# Eitech-Robotics_v11.net
KiCad netlist of a schematic drawn in EAGLE
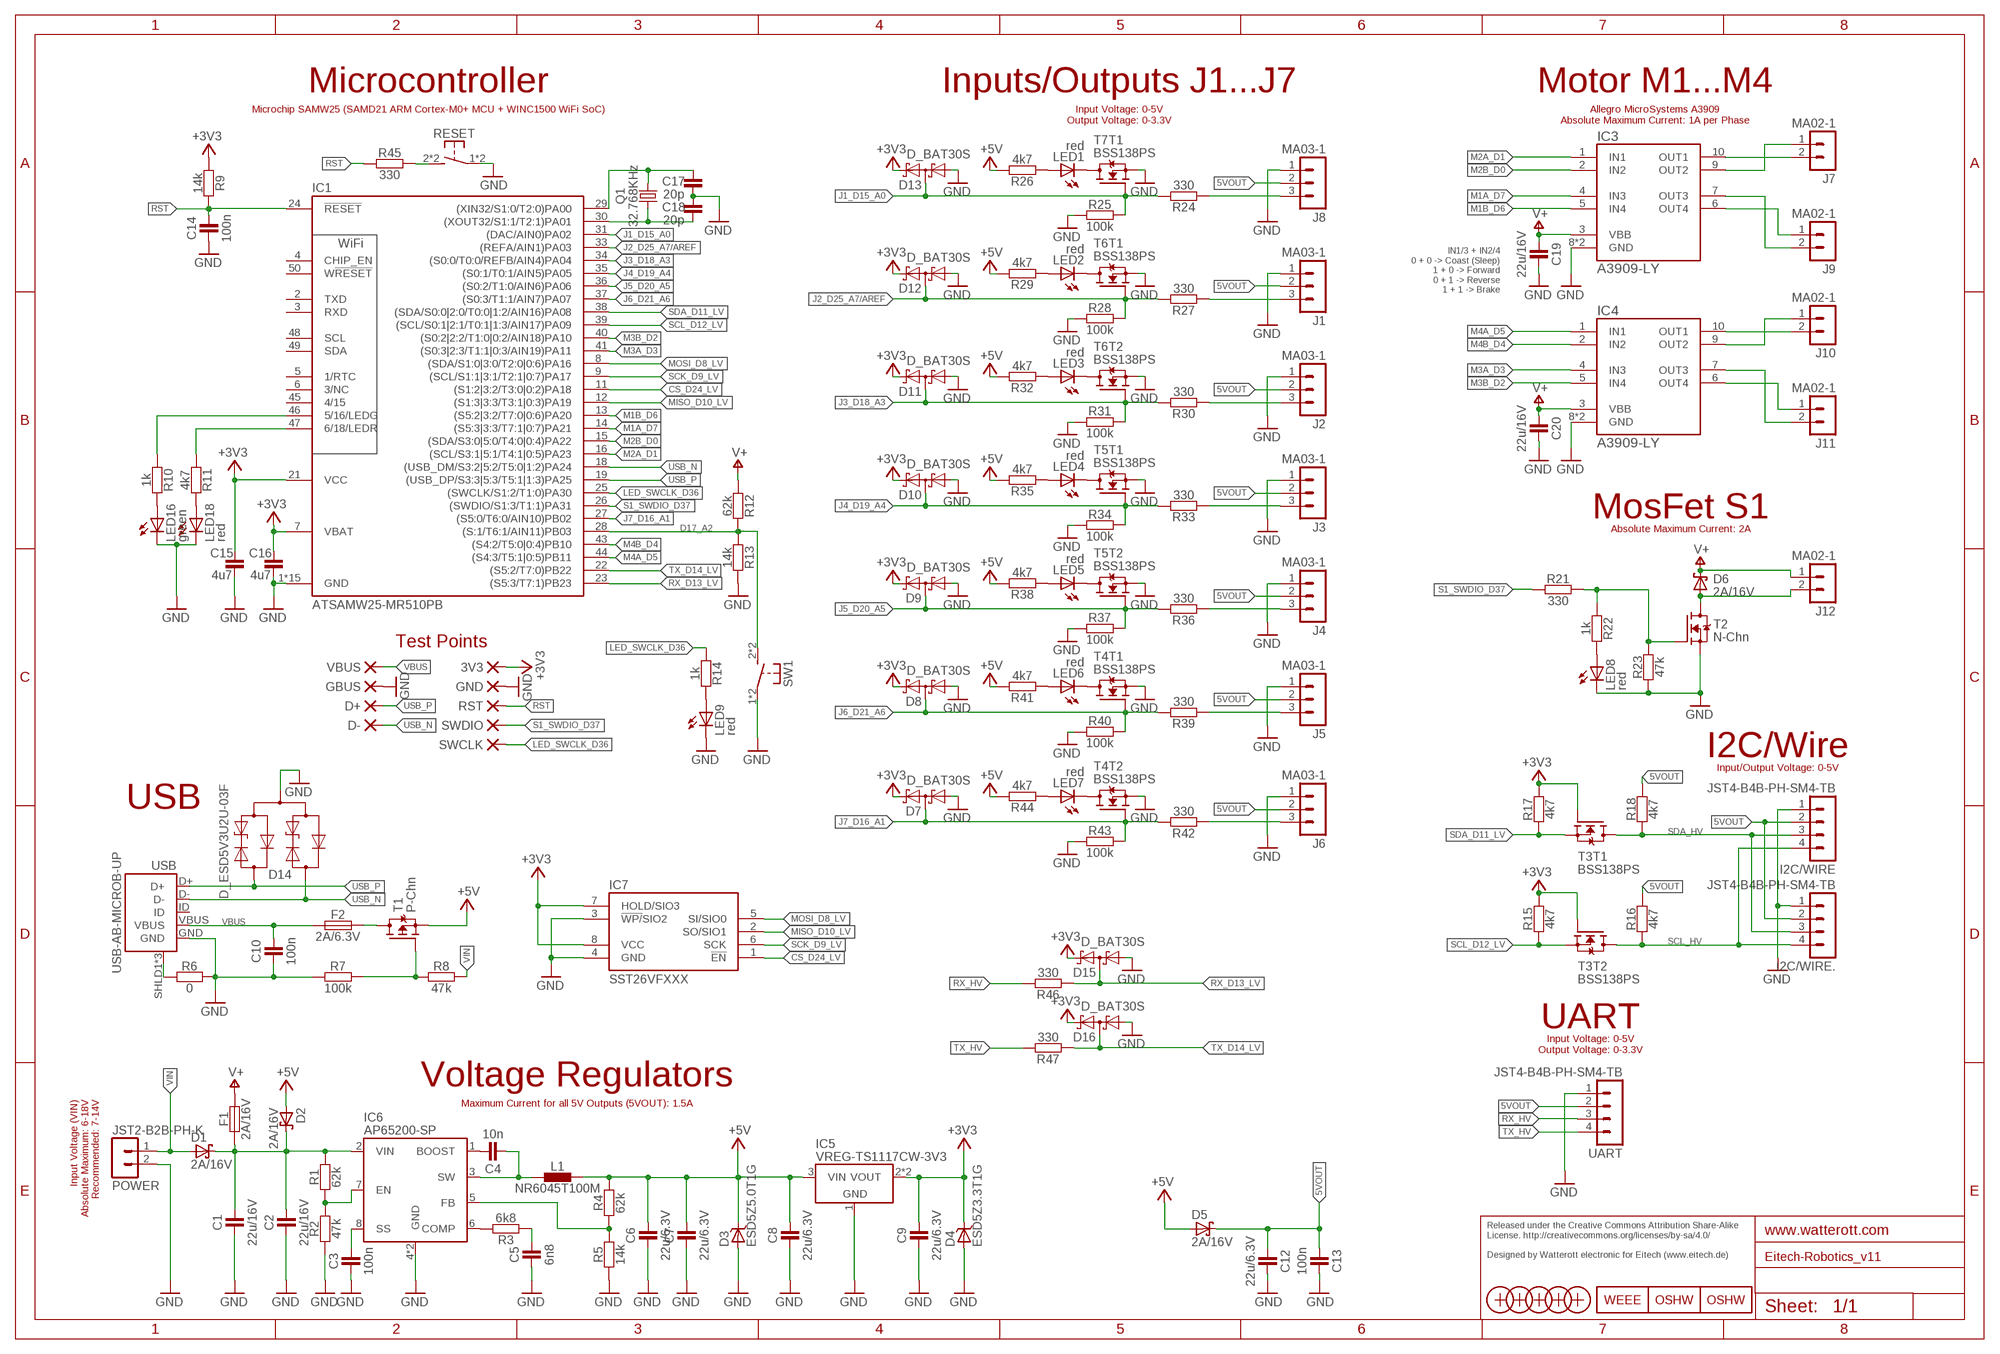
[diagram p0: schematic, sheet 1]

(export (version "E")
  (design (tool "Eeschema 10.0.6"))
  (components
    (comp (ref "3V3")
      (value "PAD-1.0_NC")
      (footprint "eagle-import:PAD-1.0_NC")
      (libsource (lib "eagle-import") (part "PAD-1.0_NC"))
    )
    (comp (ref "C1")
      (value "22u/16V")
      (footprint "eagle-import:C0805")
      (libsource (lib "eagle-import") (part "CAPACITOR-0805"))
    )
    (comp (ref "C2")
      (value "22u/16V")
      (footprint "eagle-import:C0805")
      (libsource (lib "eagle-import") (part "CAPACITOR-0805"))
    )
    (comp (ref "C3")
      (value "100n")
      (footprint "eagle-import:C0402")
      (libsource (lib "eagle-import") (part "CAPACITOR-0402"))
    )
    (comp (ref "C4")
      (value "10n")
      (footprint "eagle-import:C0402")
      (libsource (lib "eagle-import") (part "CAPACITOR-0402"))
    )
    (comp (ref "C5")
      (value "6n8")
      (footprint "eagle-import:C0402")
      (libsource (lib "eagle-import") (part "CAPACITOR-0402"))
    )
    (comp (ref "C6")
      (value "22u/6.3V")
      (footprint "eagle-import:C0805")
      (libsource (lib "eagle-import") (part "CAPACITOR-0805"))
    )
    (comp (ref "C7")
      (value "22u/6.3V")
      (footprint "eagle-import:C0805")
      (libsource (lib "eagle-import") (part "CAPACITOR-0805"))
    )
    (comp (ref "C8")
      (value "22u/6.3V")
      (footprint "eagle-import:C0805")
      (libsource (lib "eagle-import") (part "CAPACITOR-0805"))
    )
    (comp (ref "C9")
      (value "22u/6.3V")
      (footprint "eagle-import:C0805")
      (libsource (lib "eagle-import") (part "CAPACITOR-0805"))
    )
    (comp (ref "C10")
      (value "100n")
      (footprint "eagle-import:C0402")
      (libsource (lib "eagle-import") (part "CAPACITOR-0402"))
    )
    (comp (ref "C12")
      (value "22u/6.3V")
      (footprint "eagle-import:C0805")
      (libsource (lib "eagle-import") (part "CAPACITOR-0805"))
    )
    (comp (ref "C13")
      (value "100n")
      (footprint "eagle-import:C0402")
      (libsource (lib "eagle-import") (part "CAPACITOR-0402"))
    )
    (comp (ref "C14")
      (value "100n")
      (footprint "eagle-import:C0402")
      (libsource (lib "eagle-import") (part "CAPACITOR-0402"))
    )
    (comp (ref "C15")
      (value "4u7")
      (footprint "eagle-import:C0603")
      (libsource (lib "eagle-import") (part "CAPACITOR-0603"))
    )
    (comp (ref "C16")
      (value "4u7")
      (footprint "eagle-import:C0603")
      (libsource (lib "eagle-import") (part "CAPACITOR-0603"))
    )
    (comp (ref "C17")
      (value "20p")
      (footprint "eagle-import:C0402")
      (libsource (lib "eagle-import") (part "CAPACITOR-0402"))
    )
    (comp (ref "C18")
      (value "20p")
      (footprint "eagle-import:C0402")
      (libsource (lib "eagle-import") (part "CAPACITOR-0402"))
    )
    (comp (ref "C19")
      (value "22u/16V")
      (footprint "eagle-import:C0805")
      (libsource (lib "eagle-import") (part "CAPACITOR-0805"))
    )
    (comp (ref "C20")
      (value "22u/16V")
      (footprint "eagle-import:C0805")
      (libsource (lib "eagle-import") (part "CAPACITOR-0805"))
    )
    (comp (ref "D+")
      (value "PAD-1.0_NC")
      (footprint "eagle-import:PAD-1.0_NC")
      (libsource (lib "eagle-import") (part "PAD-1.0_NC"))
    )
    (comp (ref "D-")
      (value "PAD-1.0_NC")
      (footprint "eagle-import:PAD-1.0_NC")
      (libsource (lib "eagle-import") (part "PAD-1.0_NC"))
    )
    (comp (ref "D1")
      (value "2A/16V")
      (footprint "eagle-import:SOD123")
      (libsource (lib "eagle-import") (part "D_SCHOTTKY-SOD123"))
    )
    (comp (ref "D2")
      (value "2A/16V")
      (footprint "eagle-import:SOD123")
      (libsource (lib "eagle-import") (part "D_SCHOTTKY-SOD123"))
    )
    (comp (ref "D3")
      (value "ESD5Z5.0T1G")
      (footprint "eagle-import:SOD523")
      (libsource (lib "eagle-import") (part "D_TVS-SOD523"))
    )
    (comp (ref "D4")
      (value "ESD5Z3.3T1G")
      (footprint "eagle-import:SOD523")
      (libsource (lib "eagle-import") (part "D_TVS-SOD523"))
    )
    (comp (ref "D5")
      (value "2A/16V")
      (footprint "eagle-import:SOD123")
      (libsource (lib "eagle-import") (part "D_SCHOTTKY-SOD123"))
    )
    (comp (ref "D6")
      (value "2A/16V")
      (footprint "eagle-import:SOD123")
      (libsource (lib "eagle-import") (part "D_SCHOTTKY-SOD123"))
    )
    (comp (ref "D7")
      (value "D_BAT30S")
      (footprint "eagle-import:SOT323")
      (libsource (lib "eagle-import") (part "D_BAT30S"))
    )
    (comp (ref "D8")
      (value "D_BAT30S")
      (footprint "eagle-import:SOT323")
      (libsource (lib "eagle-import") (part "D_BAT30S"))
    )
    (comp (ref "D9")
      (value "D_BAT30S")
      (footprint "eagle-import:SOT323")
      (libsource (lib "eagle-import") (part "D_BAT30S"))
    )
    (comp (ref "D10")
      (value "D_BAT30S")
      (footprint "eagle-import:SOT323")
      (libsource (lib "eagle-import") (part "D_BAT30S"))
    )
    (comp (ref "D11")
      (value "D_BAT30S")
      (footprint "eagle-import:SOT323")
      (libsource (lib "eagle-import") (part "D_BAT30S"))
    )
    (comp (ref "D12")
      (value "D_BAT30S")
      (footprint "eagle-import:SOT323")
      (libsource (lib "eagle-import") (part "D_BAT30S"))
    )
    (comp (ref "D13")
      (value "D_BAT30S")
      (footprint "eagle-import:SOT323")
      (libsource (lib "eagle-import") (part "D_BAT30S"))
    )
    (comp (ref "D14")
      (value "D_ESD5V3U2U-03F")
      (footprint "eagle-import:SOT723")
      (libsource (lib "eagle-import") (part "D_ESD5V3U2U-03F"))
    )
    (comp (ref "D15")
      (value "D_BAT30S")
      (footprint "eagle-import:SOT323")
      (libsource (lib "eagle-import") (part "D_BAT30S"))
    )
    (comp (ref "D16")
      (value "D_BAT30S")
      (footprint "eagle-import:SOT323")
      (libsource (lib "eagle-import") (part "D_BAT30S"))
    )
    (comp (ref "F1")
      (value "2A/16V")
      (footprint "eagle-import:C1812")
      (libsource (lib "eagle-import") (part "FUSE-1812"))
    )
    (comp (ref "F2")
      (value "2A/6.3V")
      (footprint "eagle-import:C1206")
      (libsource (lib "eagle-import") (part "FUSE-1206"))
    )
    (comp (ref "GBUS")
      (value "PAD-1.0_NC")
      (footprint "eagle-import:PAD-1.0_NC")
      (libsource (lib "eagle-import") (part "PAD-1.0_NC"))
    )
    (comp (ref "GND")
      (value "PAD-1.0_NC")
      (footprint "eagle-import:PAD-1.0_NC")
      (libsource (lib "eagle-import") (part "PAD-1.0_NC"))
    )
    (comp (ref "I2C/WIRE")
      (value "JST4-B4B-PH-SM4-TB")
      (footprint "eagle-import:JST_B4B-PH-SM4-TB")
      (libsource (lib "eagle-import") (part "JST4-B4B-PH-SM4-TB"))
    )
    (comp (ref "I2C/WIRE.")
      (value "JST4-B4B-PH-SM4-TB")
      (footprint "eagle-import:JST_B4B-PH-SM4-TB")
      (libsource (lib "eagle-import") (part "JST4-B4B-PH-SM4-TB"))
    )
    (comp (ref "IC1")
      (value "ATSAMW25-MR510PB")
      (footprint "eagle-import:ATSAMW25-MRX10")
      (libsource (lib "eagle-import") (part "ATSAMW25-MR510PB"))
    )
    (comp (ref "IC3")
      (value "A3909-LY")
      (footprint "eagle-import:MSOP10-PAD")
      (libsource (lib "eagle-import") (part "A3909-LY"))
    )
    (comp (ref "IC4")
      (value "A3909-LY")
      (footprint "eagle-import:MSOP10-PAD")
      (libsource (lib "eagle-import") (part "A3909-LY"))
    )
    (comp (ref "IC5")
      (value "VREG-TS1117CW-3V3")
      (footprint "eagle-import:SOT223")
      (libsource (lib "eagle-import") (part "VREG-TS1117CW-3V3"))
    )
    (comp (ref "IC6")
      (value "AP65200-SP")
      (footprint "eagle-import:SO08-PAD")
      (libsource (lib "eagle-import") (part "AP65200-SP"))
    )
    (comp (ref "IC7")
      (value "SST26VFXXX")
      (footprint "eagle-import:SO08")
      (libsource (lib "eagle-import") (part "SST26VFXXX"))
    )
    (comp (ref "J1")
      (value "MA03-1")
      (footprint "eagle-import:MA03-1")
      (libsource (lib "eagle-import") (part "MA03-1"))
    )
    (comp (ref "J2")
      (value "MA03-1")
      (footprint "eagle-import:MA03-1")
      (libsource (lib "eagle-import") (part "MA03-1"))
    )
    (comp (ref "J3")
      (value "MA03-1")
      (footprint "eagle-import:MA03-1")
      (libsource (lib "eagle-import") (part "MA03-1"))
    )
    (comp (ref "J4")
      (value "MA03-1")
      (footprint "eagle-import:MA03-1")
      (libsource (lib "eagle-import") (part "MA03-1"))
    )
    (comp (ref "J5")
      (value "MA03-1")
      (footprint "eagle-import:MA03-1")
      (libsource (lib "eagle-import") (part "MA03-1"))
    )
    (comp (ref "J6")
      (value "MA03-1")
      (footprint "eagle-import:MA03-1")
      (libsource (lib "eagle-import") (part "MA03-1"))
    )
    (comp (ref "J7")
      (value "MA02-1")
      (footprint "eagle-import:MA02-1")
      (libsource (lib "eagle-import") (part "MA02-1"))
    )
    (comp (ref "J8")
      (value "MA03-1")
      (footprint "eagle-import:MA03-1")
      (libsource (lib "eagle-import") (part "MA03-1"))
    )
    (comp (ref "J9")
      (value "MA02-1")
      (footprint "eagle-import:MA02-1")
      (libsource (lib "eagle-import") (part "MA02-1"))
    )
    (comp (ref "J10")
      (value "MA02-1")
      (footprint "eagle-import:MA02-1")
      (libsource (lib "eagle-import") (part "MA02-1"))
    )
    (comp (ref "J11")
      (value "MA02-1")
      (footprint "eagle-import:MA02-1")
      (libsource (lib "eagle-import") (part "MA02-1"))
    )
    (comp (ref "J12")
      (value "MA02-1")
      (footprint "eagle-import:MA02-1")
      (libsource (lib "eagle-import") (part "MA02-1"))
    )
    (comp (ref "L1")
      (value "NR6045T100M")
      (footprint "eagle-import:L_NR60XX")
      (libsource (lib "eagle-import") (part "INDUCTOR-NR60XX"))
    )
    (comp (ref "LED1")
      (value "red")
      (footprint "eagle-import:C0603")
      (libsource (lib "eagle-import") (part "LED-0603"))
    )
    (comp (ref "LED2")
      (value "red")
      (footprint "eagle-import:C0603")
      (libsource (lib "eagle-import") (part "LED-0603"))
    )
    (comp (ref "LED3")
      (value "red")
      (footprint "eagle-import:C0603")
      (libsource (lib "eagle-import") (part "LED-0603"))
    )
    (comp (ref "LED4")
      (value "red")
      (footprint "eagle-import:C0603")
      (libsource (lib "eagle-import") (part "LED-0603"))
    )
    (comp (ref "LED5")
      (value "red")
      (footprint "eagle-import:C0603")
      (libsource (lib "eagle-import") (part "LED-0603"))
    )
    (comp (ref "LED6")
      (value "red")
      (footprint "eagle-import:C0603")
      (libsource (lib "eagle-import") (part "LED-0603"))
    )
    (comp (ref "LED7")
      (value "red")
      (footprint "eagle-import:C0603")
      (libsource (lib "eagle-import") (part "LED-0603"))
    )
    (comp (ref "LED8")
      (value "red")
      (footprint "eagle-import:C0603")
      (libsource (lib "eagle-import") (part "LED-0603"))
    )
    (comp (ref "LED9")
      (value "red")
      (footprint "eagle-import:C0603")
      (libsource (lib "eagle-import") (part "LED-0603"))
    )
    (comp (ref "LED16")
      (value "green")
      (footprint "eagle-import:C0603")
      (libsource (lib "eagle-import") (part "LED-0603"))
    )
    (comp (ref "LED18")
      (value "red")
      (footprint "eagle-import:C0603")
      (libsource (lib "eagle-import") (part "LED-0603"))
    )
    (comp (ref "LOGO1")
      (value "OSHW_LOGOX0100")
      (footprint "eagle-import:OSHW_6X100")
      (libsource (lib "eagle-import") (part "OSHW_LOGOX0100"))
    )
    (comp (ref "LOGO2")
      (value "OSHW_LOGOX0150")
      (footprint "eagle-import:OSHW_6X150")
      (libsource (lib "eagle-import") (part "OSHW_LOGOX0150"))
    )
    (comp (ref "LOGO4")
      (value "WEEE_LOGO-S")
      (footprint "eagle-import:WEEE_TPLAC_S")
      (libsource (lib "eagle-import") (part "WEEE_LOGO-S"))
    )
    (comp (ref "POWER")
      (value "JST2-B2B-PH-K")
      (footprint "eagle-import:JST_B2B-PH-K")
      (libsource (lib "eagle-import") (part "JST2-B2B-PH-K"))
    )
    (comp (ref "Q1")
      (value "32.768KHz")
      (footprint "eagle-import:CRYSTAL_ZM315")
      (libsource (lib "eagle-import") (part "CRYSTAL-ZM315"))
    )
    (comp (ref "R1")
      (value "62k")
      (footprint "eagle-import:C0402")
      (libsource (lib "eagle-import") (part "RESISTOR-0402"))
    )
    (comp (ref "R2")
      (value "47k")
      (footprint "eagle-import:C0402")
      (libsource (lib "eagle-import") (part "RESISTOR-0402"))
    )
    (comp (ref "R3")
      (value "6k8")
      (footprint "eagle-import:C0402")
      (libsource (lib "eagle-import") (part "RESISTOR-0402"))
    )
    (comp (ref "R4")
      (value "62k")
      (footprint "eagle-import:C0402")
      (libsource (lib "eagle-import") (part "RESISTOR-0402"))
    )
    (comp (ref "R5")
      (value "14k")
      (footprint "eagle-import:C0402")
      (libsource (lib "eagle-import") (part "RESISTOR-0402"))
    )
    (comp (ref "R6")
      (value "0")
      (footprint "eagle-import:C0402")
      (libsource (lib "eagle-import") (part "RESISTOR-0402"))
    )
    (comp (ref "R7")
      (value "100k")
      (footprint "eagle-import:C0402")
      (libsource (lib "eagle-import") (part "RESISTOR-0402"))
    )
    (comp (ref "R8")
      (value "47k")
      (footprint "eagle-import:C0402")
      (libsource (lib "eagle-import") (part "RESISTOR-0402"))
    )
    (comp (ref "R9")
      (value "14k")
      (footprint "eagle-import:C0402")
      (libsource (lib "eagle-import") (part "RESISTOR-0402"))
    )
    (comp (ref "R10")
      (value "1k")
      (footprint "eagle-import:C0402")
      (libsource (lib "eagle-import") (part "RESISTOR-0402"))
    )
    (comp (ref "R11")
      (value "4k7")
      (footprint "eagle-import:C0402")
      (libsource (lib "eagle-import") (part "RESISTOR-0402"))
    )
    (comp (ref "R12")
      (value "62k")
      (footprint "eagle-import:C0402")
      (libsource (lib "eagle-import") (part "RESISTOR-0402"))
    )
    (comp (ref "R13")
      (value "14k")
      (footprint "eagle-import:C0402")
      (libsource (lib "eagle-import") (part "RESISTOR-0402"))
    )
    (comp (ref "R14")
      (value "1k")
      (footprint "eagle-import:C0402")
      (libsource (lib "eagle-import") (part "RESISTOR-0402"))
    )
    (comp (ref "R15")
      (value "4k7")
      (footprint "eagle-import:C0402")
      (libsource (lib "eagle-import") (part "RESISTOR-0402"))
    )
    (comp (ref "R16")
      (value "4k7")
      (footprint "eagle-import:C0402")
      (libsource (lib "eagle-import") (part "RESISTOR-0402"))
    )
    (comp (ref "R17")
      (value "4k7")
      (footprint "eagle-import:C0402")
      (libsource (lib "eagle-import") (part "RESISTOR-0402"))
    )
    (comp (ref "R18")
      (value "4k7")
      (footprint "eagle-import:C0402")
      (libsource (lib "eagle-import") (part "RESISTOR-0402"))
    )
    (comp (ref "R21")
      (value "330")
      (footprint "eagle-import:C0402")
      (libsource (lib "eagle-import") (part "RESISTOR-0402"))
    )
    (comp (ref "R22")
      (value "1k")
      (footprint "eagle-import:C0402")
      (libsource (lib "eagle-import") (part "RESISTOR-0402"))
    )
    (comp (ref "R23")
      (value "47k")
      (footprint "eagle-import:C0402")
      (libsource (lib "eagle-import") (part "RESISTOR-0402"))
    )
    (comp (ref "R24")
      (value "330")
      (footprint "eagle-import:C0402")
      (libsource (lib "eagle-import") (part "RESISTOR-0402"))
    )
    (comp (ref "R25")
      (value "100k")
      (footprint "eagle-import:C0402")
      (libsource (lib "eagle-import") (part "RESISTOR-0402"))
    )
    (comp (ref "R26")
      (value "4k7")
      (footprint "eagle-import:C0402")
      (libsource (lib "eagle-import") (part "RESISTOR-0402"))
    )
    (comp (ref "R27")
      (value "330")
      (footprint "eagle-import:C0402")
      (libsource (lib "eagle-import") (part "RESISTOR-0402"))
    )
    (comp (ref "R28")
      (value "100k")
      (footprint "eagle-import:C0402")
      (libsource (lib "eagle-import") (part "RESISTOR-0402"))
    )
    (comp (ref "R29")
      (value "4k7")
      (footprint "eagle-import:C0402")
      (libsource (lib "eagle-import") (part "RESISTOR-0402"))
    )
    (comp (ref "R30")
      (value "330")
      (footprint "eagle-import:C0402")
      (libsource (lib "eagle-import") (part "RESISTOR-0402"))
    )
    (comp (ref "R31")
      (value "100k")
      (footprint "eagle-import:C0402")
      (libsource (lib "eagle-import") (part "RESISTOR-0402"))
    )
    (comp (ref "R32")
      (value "4k7")
      (footprint "eagle-import:C0402")
      (libsource (lib "eagle-import") (part "RESISTOR-0402"))
    )
    (comp (ref "R33")
      (value "330")
      (footprint "eagle-import:C0402")
      (libsource (lib "eagle-import") (part "RESISTOR-0402"))
    )
    (comp (ref "R34")
      (value "100k")
      (footprint "eagle-import:C0402")
      (libsource (lib "eagle-import") (part "RESISTOR-0402"))
    )
    (comp (ref "R35")
      (value "4k7")
      (footprint "eagle-import:C0402")
      (libsource (lib "eagle-import") (part "RESISTOR-0402"))
    )
    (comp (ref "R36")
      (value "330")
      (footprint "eagle-import:C0402")
      (libsource (lib "eagle-import") (part "RESISTOR-0402"))
    )
    (comp (ref "R37")
      (value "100k")
      (footprint "eagle-import:C0402")
      (libsource (lib "eagle-import") (part "RESISTOR-0402"))
    )
    (comp (ref "R38")
      (value "4k7")
      (footprint "eagle-import:C0402")
      (libsource (lib "eagle-import") (part "RESISTOR-0402"))
    )
    (comp (ref "R39")
      (value "330")
      (footprint "eagle-import:C0402")
      (libsource (lib "eagle-import") (part "RESISTOR-0402"))
    )
    (comp (ref "R40")
      (value "100k")
      (footprint "eagle-import:C0402")
      (libsource (lib "eagle-import") (part "RESISTOR-0402"))
    )
    (comp (ref "R41")
      (value "4k7")
      (footprint "eagle-import:C0402")
      (libsource (lib "eagle-import") (part "RESISTOR-0402"))
    )
    (comp (ref "R42")
      (value "330")
      (footprint "eagle-import:C0402")
      (libsource (lib "eagle-import") (part "RESISTOR-0402"))
    )
    (comp (ref "R43")
      (value "100k")
      (footprint "eagle-import:C0402")
      (libsource (lib "eagle-import") (part "RESISTOR-0402"))
    )
    (comp (ref "R44")
      (value "4k7")
      (footprint "eagle-import:C0402")
      (libsource (lib "eagle-import") (part "RESISTOR-0402"))
    )
    (comp (ref "R45")
      (value "330")
      (footprint "eagle-import:C0402")
      (libsource (lib "eagle-import") (part "RESISTOR-0402"))
    )
    (comp (ref "R46")
      (value "330")
      (footprint "eagle-import:C0402")
      (libsource (lib "eagle-import") (part "RESISTOR-0402"))
    )
    (comp (ref "R47")
      (value "330")
      (footprint "eagle-import:C0402")
      (libsource (lib "eagle-import") (part "RESISTOR-0402"))
    )
    (comp (ref "RESET")
      (value "SW-TACTILE-TL3305C")
      (footprint "eagle-import:TL3305")
      (fields (field (name "MPN") "TL3305C"))
      (libsource (lib "eagle-import") (part "SW-TACTILE-TL3305"))
    )
    (comp (ref "RST")
      (value "PAD-1.0_NC")
      (footprint "eagle-import:PAD-1.0_NC")
      (libsource (lib "eagle-import") (part "PAD-1.0_NC"))
    )
    (comp (ref "SW1")
      (value "SW-TACTILE-TL3305C")
      (footprint "eagle-import:TL3305")
      (fields (field (name "MPN") "TL3305C"))
      (libsource (lib "eagle-import") (part "SW-TACTILE-TL3305"))
    )
    (comp (ref "SWCLK")
      (value "PAD-1.0_NC")
      (footprint "eagle-import:PAD-1.0_NC")
      (libsource (lib "eagle-import") (part "PAD-1.0_NC"))
    )
    (comp (ref "SWDIO")
      (value "PAD-1.0_NC")
      (footprint "eagle-import:PAD-1.0_NC")
      (libsource (lib "eagle-import") (part "PAD-1.0_NC"))
    )
    (comp (ref "T1")
      (value "P-Chn")
      (footprint "eagle-import:SOT23")
      (libsource (lib "eagle-import") (part "MOSFET-P-SOT23"))
    )
    (comp (ref "T2")
      (value "N-Chn")
      (footprint "eagle-import:SOT23")
      (libsource (lib "eagle-import") (part "MOSFET-N-SOT23"))
    )
    (comp (ref "T3")
      (value "BSS138PS")
      (footprint "eagle-import:SOT363")
      (libsource (lib "eagle-import") (part "BSS138PS"))
    )
    (comp (ref "T4")
      (value "BSS138PS")
      (footprint "eagle-import:SOT363")
      (libsource (lib "eagle-import") (part "BSS138PS"))
    )
    (comp (ref "T5")
      (value "BSS138PS")
      (footprint "eagle-import:SOT363")
      (libsource (lib "eagle-import") (part "BSS138PS"))
    )
    (comp (ref "T6")
      (value "BSS138PS")
      (footprint "eagle-import:SOT363")
      (libsource (lib "eagle-import") (part "BSS138PS"))
    )
    (comp (ref "T7")
      (value "BSS138PS")
      (footprint "eagle-import:SOT363")
      (libsource (lib "eagle-import") (part "BSS138PS"))
    )
    (comp (ref "UART")
      (value "JST4-B4B-PH-SM4-TB")
      (footprint "eagle-import:JST_B4B-PH-SM4-TB")
      (libsource (lib "eagle-import") (part "JST4-B4B-PH-SM4-TB"))
    )
    (comp (ref "USB")
      (value "USB-AB-MICROB-UP")
      (footprint "eagle-import:USB-MICROB-1051330011")
      (libsource (lib "eagle-import") (part "USB-AB-MICROB-UP"))
    )
    (comp (ref "VBUS")
      (value "PAD-1.0_NC")
      (footprint "eagle-import:PAD-1.0_NC")
      (libsource (lib "eagle-import") (part "PAD-1.0_NC"))
    )
    (comp (ref "X1")
      (value "PASSER-07")
      (footprint "eagle-import:PASSER_07MM")
      (libsource (lib "eagle-import") (part "PASSER-07"))
    )
    (comp (ref "X2")
      (value "PASSER-07")
      (footprint "eagle-import:PASSER_07MM")
      (libsource (lib "eagle-import") (part "PASSER-07"))
    )
    (comp (ref "X3")
      (value "PASSER-07")
      (footprint "eagle-import:PASSER_07MM")
      (libsource (lib "eagle-import") (part "PASSER-07"))
    )
    (comp (ref "X4")
      (value "PASSER-07")
      (footprint "eagle-import:PASSER_07MM")
      (libsource (lib "eagle-import") (part "PASSER-07"))
    )
    (comp (ref "X5")
      (value "PASSER-04")
      (footprint "eagle-import:PASSER_04MM")
      (libsource (lib "eagle-import") (part "PASSER-04"))
    )
  )
  (nets
    (net (code "1") (name "+3V3") (class "Default")
      (node (ref "3V3") (pin "1") (pinfunction "P_1") (pintype "passive"))
      (node (ref "C15") (pin "2") (pinfunction "2_2") (pintype "passive"))
      (node (ref "C16") (pin "2") (pinfunction "2_2") (pintype "passive"))
      (node (ref "C9") (pin "2") (pinfunction "2_2") (pintype "passive"))
      (node (ref "D10") (pin "2") (pinfunction "C_2") (pintype "passive"))
      (node (ref "D11") (pin "2") (pinfunction "C_2") (pintype "passive"))
      (node (ref "D12") (pin "2") (pinfunction "C_2") (pintype "passive"))
      (node (ref "D13") (pin "2") (pinfunction "C_2") (pintype "passive"))
      (node (ref "D15") (pin "2") (pinfunction "C_2") (pintype "passive"))
      (node (ref "D16") (pin "2") (pinfunction "C_2") (pintype "passive"))
      (node (ref "D4") (pin "C") (pinfunction "C_C") (pintype "passive"))
      (node (ref "D7") (pin "2") (pinfunction "C_2") (pintype "passive"))
      (node (ref "D8") (pin "2") (pinfunction "C_2") (pintype "passive"))
      (node (ref "D9") (pin "2") (pinfunction "C_2") (pintype "passive"))
      (node (ref "IC1") (pin "21") (pinfunction "VCC_21") (pintype "power_in"))
      (node (ref "IC1") (pin "7") (pinfunction "VBAT_7") (pintype "power_in"))
      (node (ref "IC5") (pin "2") (pinfunction "VOUT_2") (pintype "power_in"))
      (node (ref "IC5") (pin "4") (pinfunction "VOUT_4") (pintype "power_in"))
      (node (ref "IC7") (pin "7") (pinfunction "HOLD/SIO3_7") (pintype "input"))
      (node (ref "IC7") (pin "8") (pinfunction "VCC_8") (pintype "power_in"))
      (node (ref "R15") (pin "2") (pinfunction "2_2") (pintype "passive"))
      (node (ref "R17") (pin "2") (pinfunction "2_2") (pintype "passive"))
      (node (ref "R9") (pin "1") (pinfunction "1_1") (pintype "passive"))
      (node (ref "T3") (pin "2") (pinfunction "G_2") (pintype "passive"))
      (node (ref "T3") (pin "5") (pinfunction "G_5") (pintype "passive"))
    )
    (net (code "2") (name "+5V") (class "Default")
      (node (ref "C6") (pin "2") (pinfunction "2_2") (pintype "passive"))
      (node (ref "C7") (pin "2") (pinfunction "2_2") (pintype "passive"))
      (node (ref "C8") (pin "2") (pinfunction "2_2") (pintype "passive"))
      (node (ref "D2") (pin "A") (pinfunction "A_A") (pintype "passive"))
      (node (ref "D3") (pin "C") (pinfunction "C_C") (pintype "passive"))
      (node (ref "D5") (pin "A") (pinfunction "A_A") (pintype "passive"))
      (node (ref "IC5") (pin "3") (pinfunction "VIN_3") (pintype "power_in"))
      (node (ref "L1") (pin "2") (pinfunction "2_2") (pintype "passive"))
      (node (ref "R26") (pin "2") (pinfunction "2_2") (pintype "passive"))
      (node (ref "R29") (pin "2") (pinfunction "2_2") (pintype "passive"))
      (node (ref "R32") (pin "2") (pinfunction "2_2") (pintype "passive"))
      (node (ref "R35") (pin "2") (pinfunction "2_2") (pintype "passive"))
      (node (ref "R38") (pin "2") (pinfunction "2_2") (pintype "passive"))
      (node (ref "R4") (pin "2") (pinfunction "2_2") (pintype "passive"))
      (node (ref "R41") (pin "2") (pinfunction "2_2") (pintype "passive"))
      (node (ref "R44") (pin "2") (pinfunction "2_2") (pintype "passive"))
      (node (ref "T1") (pin "2") (pinfunction "S_2") (pintype "passive"))
    )
    (net (code "3") (name "/D17_A2") (class "Default")
      (node (ref "IC1") (pin "28") (pinfunction "(S:1/T6:1/AIN11)PB03_28") (pintype "bidirectional"))
      (node (ref "R12") (pin "2") (pinfunction "2_2") (pintype "passive"))
      (node (ref "R13") (pin "1") (pinfunction "1_1") (pintype "passive"))
      (node (ref "SW1") (pin "2") (pinfunction "S1_2") (pintype "passive"))
      (node (ref "SW1") (pin "3") (pinfunction "S1_3") (pintype "passive"))
    )
    (net (code "4") (name "/SCL_HV") (class "Default")
      (node (ref "I2C/WIRE") (pin "4") (pinfunction "4_4") (pintype "passive"))
      (node (ref "I2C/WIRE.") (pin "4") (pinfunction "4_4") (pintype "passive"))
      (node (ref "R16") (pin "1") (pinfunction "1_1") (pintype "passive"))
      (node (ref "T3") (pin "3") (pinfunction "D_3") (pintype "passive"))
    )
    (net (code "5") (name "/SDA_HV") (class "Default")
      (node (ref "I2C/WIRE") (pin "3") (pinfunction "3_3") (pintype "passive"))
      (node (ref "I2C/WIRE.") (pin "3") (pinfunction "3_3") (pintype "passive"))
      (node (ref "R18") (pin "1") (pinfunction "1_1") (pintype "passive"))
      (node (ref "T3") (pin "6") (pinfunction "D_6") (pintype "passive"))
    )
    (net (code "6") (name "5VOUT") (class "Default")
      (node (ref "C12") (pin "2") (pinfunction "2_2") (pintype "passive"))
      (node (ref "C13") (pin "2") (pinfunction "2_2") (pintype "passive"))
      (node (ref "D5") (pin "C") (pinfunction "C_C") (pintype "passive"))
      (node (ref "I2C/WIRE") (pin "2") (pinfunction "2_2") (pintype "passive"))
      (node (ref "I2C/WIRE.") (pin "2") (pinfunction "2_2") (pintype "passive"))
      (node (ref "J1") (pin "2") (pinfunction "2_2") (pintype "passive"))
      (node (ref "J2") (pin "2") (pinfunction "2_2") (pintype "passive"))
      (node (ref "J3") (pin "2") (pinfunction "2_2") (pintype "passive"))
      (node (ref "J4") (pin "2") (pinfunction "2_2") (pintype "passive"))
      (node (ref "J5") (pin "2") (pinfunction "2_2") (pintype "passive"))
      (node (ref "J6") (pin "2") (pinfunction "2_2") (pintype "passive"))
      (node (ref "J8") (pin "2") (pinfunction "2_2") (pintype "passive"))
      (node (ref "R16") (pin "2") (pinfunction "2_2") (pintype "passive"))
      (node (ref "R18") (pin "2") (pinfunction "2_2") (pintype "passive"))
      (node (ref "UART") (pin "2") (pinfunction "2_2") (pintype "passive"))
    )
    (net (code "7") (name "CS_D24_LV") (class "Default")
      (node (ref "IC1") (pin "11") (pinfunction "(S1:2|3:2/T3:0|0:2)PA18_11") (pintype "bidirectional"))
      (node (ref "IC7") (pin "1") (pinfunction "~{EN}_1") (pintype "bidirectional"))
    )
    (net (code "8") (name "GND") (class "Default")
      (node (ref "C1") (pin "1") (pinfunction "1_1") (pintype "passive"))
      (node (ref "C10") (pin "1") (pinfunction "1_1") (pintype "passive"))
      (node (ref "C12") (pin "1") (pinfunction "1_1") (pintype "passive"))
      (node (ref "C13") (pin "1") (pinfunction "1_1") (pintype "passive"))
      (node (ref "C14") (pin "1") (pinfunction "1_1") (pintype "passive"))
      (node (ref "C15") (pin "1") (pinfunction "1_1") (pintype "passive"))
      (node (ref "C16") (pin "1") (pinfunction "1_1") (pintype "passive"))
      (node (ref "C17") (pin "2") (pinfunction "2_2") (pintype "passive"))
      (node (ref "C18") (pin "2") (pinfunction "2_2") (pintype "passive"))
      (node (ref "C19") (pin "2") (pinfunction "2_2") (pintype "passive"))
      (node (ref "C2") (pin "1") (pinfunction "1_1") (pintype "passive"))
      (node (ref "C20") (pin "2") (pinfunction "2_2") (pintype "passive"))
      (node (ref "C3") (pin "1") (pinfunction "1_1") (pintype "passive"))
      (node (ref "C5") (pin "1") (pinfunction "1_1") (pintype "passive"))
      (node (ref "C6") (pin "1") (pinfunction "1_1") (pintype "passive"))
      (node (ref "C7") (pin "1") (pinfunction "1_1") (pintype "passive"))
      (node (ref "C8") (pin "1") (pinfunction "1_1") (pintype "passive"))
      (node (ref "C9") (pin "1") (pinfunction "1_1") (pintype "passive"))
      (node (ref "D10") (pin "1") (pinfunction "A_1") (pintype "passive"))
      (node (ref "D11") (pin "1") (pinfunction "A_1") (pintype "passive"))
      (node (ref "D12") (pin "1") (pinfunction "A_1") (pintype "passive"))
      (node (ref "D13") (pin "1") (pinfunction "A_1") (pintype "passive"))
      (node (ref "D14") (pin "3") (pinfunction "A_3") (pintype "passive"))
      (node (ref "D15") (pin "1") (pinfunction "A_1") (pintype "passive"))
      (node (ref "D16") (pin "1") (pinfunction "A_1") (pintype "passive"))
      (node (ref "D3") (pin "A") (pinfunction "A_A") (pintype "passive"))
      (node (ref "D4") (pin "A") (pinfunction "A_A") (pintype "passive"))
      (node (ref "D7") (pin "1") (pinfunction "A_1") (pintype "passive"))
      (node (ref "D8") (pin "1") (pinfunction "A_1") (pintype "passive"))
      (node (ref "D9") (pin "1") (pinfunction "A_1") (pintype "passive"))
      (node (ref "GBUS") (pin "1") (pinfunction "P_1") (pintype "passive"))
      (node (ref "GND") (pin "1") (pinfunction "P_1") (pintype "passive"))
      (node (ref "I2C/WIRE") (pin "1") (pinfunction "1_1") (pintype "passive"))
      (node (ref "I2C/WIRE.") (pin "1") (pinfunction "1_1") (pintype "passive"))
      (node (ref "IC1") (pin "1") (pinfunction "GND_1") (pintype "power_in"))
      (node (ref "IC1") (pin "10") (pinfunction "GND_10") (pintype "power_in"))
      (node (ref "IC1") (pin "17") (pinfunction "GND_17") (pintype "power_in"))
      (node (ref "IC1") (pin "20") (pinfunction "GND_20") (pintype "power_in"))
      (node (ref "IC1") (pin "32") (pinfunction "GND_32") (pintype "power_in"))
      (node (ref "IC1") (pin "42") (pinfunction "GND_42") (pintype "power_in"))
      (node (ref "IC1") (pin "51") (pinfunction "GND_51") (pintype "power_in"))
      (node (ref "IC1") (pin "GND@1") (pinfunction "GND_GND@1") (pintype "power_in"))
      (node (ref "IC1") (pin "GND@2") (pinfunction "GND_GND@2") (pintype "power_in"))
      (node (ref "IC1") (pin "GND@3") (pinfunction "GND_GND@3") (pintype "power_in"))
      (node (ref "IC1") (pin "GND@4") (pinfunction "GND_GND@4") (pintype "power_in"))
      (node (ref "IC1") (pin "GND@5") (pinfunction "GND_GND@5") (pintype "power_in"))
      (node (ref "IC1") (pin "GND@6") (pinfunction "GND_GND@6") (pintype "power_in"))
      (node (ref "IC1") (pin "GND@7") (pinfunction "GND_GND@7") (pintype "power_in"))
      (node (ref "IC1") (pin "GND@8") (pinfunction "GND_GND@8") (pintype "power_in"))
      (node (ref "IC3") (pin "8") (pinfunction "GND_8") (pintype "power_in"))
      (node (ref "IC3") (pin "TP") (pinfunction "GND_TP") (pintype "power_in"))
      (node (ref "IC4") (pin "8") (pinfunction "GND_8") (pintype "power_in"))
      (node (ref "IC4") (pin "TP") (pinfunction "GND_TP") (pintype "power_in"))
      (node (ref "IC5") (pin "1") (pinfunction "GND_1") (pintype "power_in"))
      (node (ref "IC6") (pin "4") (pinfunction "GND_4") (pintype "power_in"))
      (node (ref "IC6") (pin "TP") (pinfunction "GND_TP") (pintype "power_in"))
      (node (ref "IC7") (pin "3") (pinfunction "~{WP/}SIO2_3") (pintype "input"))
      (node (ref "IC7") (pin "4") (pinfunction "GND_4") (pintype "power_in"))
      (node (ref "J1") (pin "1") (pinfunction "1_1") (pintype "passive"))
      (node (ref "J2") (pin "1") (pinfunction "1_1") (pintype "passive"))
      (node (ref "J3") (pin "1") (pinfunction "1_1") (pintype "passive"))
      (node (ref "J4") (pin "1") (pinfunction "1_1") (pintype "passive"))
      (node (ref "J5") (pin "1") (pinfunction "1_1") (pintype "passive"))
      (node (ref "J6") (pin "1") (pinfunction "1_1") (pintype "passive"))
      (node (ref "J8") (pin "1") (pinfunction "1_1") (pintype "passive"))
      (node (ref "LED16") (pin "C") (pinfunction "C_C") (pintype "passive"))
      (node (ref "LED18") (pin "C") (pinfunction "C_C") (pintype "passive"))
      (node (ref "LED8") (pin "C") (pinfunction "C_C") (pintype "passive"))
      (node (ref "LED9") (pin "C") (pinfunction "C_C") (pintype "passive"))
      (node (ref "POWER") (pin "2") (pinfunction "2_2") (pintype "passive"))
      (node (ref "R13") (pin "2") (pinfunction "2_2") (pintype "passive"))
      (node (ref "R2") (pin "1") (pinfunction "1_1") (pintype "passive"))
      (node (ref "R23") (pin "1") (pinfunction "1_1") (pintype "passive"))
      (node (ref "R25") (pin "1") (pinfunction "1_1") (pintype "passive"))
      (node (ref "R28") (pin "1") (pinfunction "1_1") (pintype "passive"))
      (node (ref "R31") (pin "1") (pinfunction "1_1") (pintype "passive"))
      (node (ref "R34") (pin "1") (pinfunction "1_1") (pintype "passive"))
      (node (ref "R37") (pin "1") (pinfunction "1_1") (pintype "passive"))
      (node (ref "R40") (pin "1") (pinfunction "1_1") (pintype "passive"))
      (node (ref "R43") (pin "1") (pinfunction "1_1") (pintype "passive"))
      (node (ref "R5") (pin "1") (pinfunction "1_1") (pintype "passive"))
      (node (ref "R6") (pin "1") (pinfunction "1_1") (pintype "passive"))
      (node (ref "R7") (pin "1") (pinfunction "1_1") (pintype "passive"))
      (node (ref "RESET") (pin "1") (pinfunction "P1_1") (pintype "passive"))
      (node (ref "RESET") (pin "4") (pinfunction "P1_4") (pintype "passive"))
      (node (ref "SW1") (pin "1") (pinfunction "P1_1") (pintype "passive"))
      (node (ref "SW1") (pin "4") (pinfunction "P1_4") (pintype "passive"))
      (node (ref "T2") (pin "2") (pinfunction "S_2") (pintype "passive"))
      (node (ref "T4") (pin "1") (pinfunction "S_1") (pintype "passive"))
      (node (ref "T4") (pin "4") (pinfunction "S_4") (pintype "passive"))
      (node (ref "T5") (pin "1") (pinfunction "S_1") (pintype "passive"))
      (node (ref "T5") (pin "4") (pinfunction "S_4") (pintype "passive"))
      (node (ref "T6") (pin "1") (pinfunction "S_1") (pintype "passive"))
      (node (ref "T6") (pin "4") (pinfunction "S_4") (pintype "passive"))
      (node (ref "T7") (pin "1") (pinfunction "S_1") (pintype "passive"))
      (node (ref "UART") (pin "1") (pinfunction "1_1") (pintype "passive"))
      (node (ref "USB") (pin "GND") (pinfunction "GND_GND") (pintype "power_in"))
    )
    (net (code "9") (name "J1_D15_A0") (class "Default")
      (node (ref "D13") (pin "3") (pinfunction "CA_3") (pintype "passive"))
      (node (ref "IC1") (pin "31") (pinfunction "(DAC/AIN0)PA02_31") (pintype "bidirectional"))
      (node (ref "R24") (pin "2") (pinfunction "2_2") (pintype "passive"))
      (node (ref "R25") (pin "2") (pinfunction "2_2") (pintype "passive"))
      (node (ref "T7") (pin "2") (pinfunction "G_2") (pintype "passive"))
    )
    (net (code "10") (name "J2_D25_A7{slash}AREF") (class "Default")
      (node (ref "D12") (pin "3") (pinfunction "CA_3") (pintype "passive"))
      (node (ref "IC1") (pin "33") (pinfunction "(REFA/AIN1)PA03_33") (pintype "bidirectional"))
      (node (ref "R27") (pin "2") (pinfunction "2_2") (pintype "passive"))
      (node (ref "R28") (pin "2") (pinfunction "2_2") (pintype "passive"))
      (node (ref "T6") (pin "2") (pinfunction "G_2") (pintype "passive"))
    )
    (net (code "11") (name "J3_D18_A3") (class "Default")
      (node (ref "D11") (pin "3") (pinfunction "CA_3") (pintype "passive"))
      (node (ref "IC1") (pin "34") (pinfunction "(S0:0/T0:0/REFB/AIN4)PA04_34") (pintype "bidirectional"))
      (node (ref "R30") (pin "2") (pinfunction "2_2") (pintype "passive"))
      (node (ref "R31") (pin "2") (pinfunction "2_2") (pintype "passive"))
      (node (ref "T6") (pin "5") (pinfunction "G_5") (pintype "passive"))
    )
    (net (code "12") (name "J4_D19_A4") (class "Default")
      (node (ref "D10") (pin "3") (pinfunction "CA_3") (pintype "passive"))
      (node (ref "IC1") (pin "35") (pinfunction "(S0:1/T0:1/AIN5)PA05_35") (pintype "bidirectional"))
      (node (ref "R33") (pin "2") (pinfunction "2_2") (pintype "passive"))
      (node (ref "R34") (pin "2") (pinfunction "2_2") (pintype "passive"))
      (node (ref "T5") (pin "2") (pinfunction "G_2") (pintype "passive"))
    )
    (net (code "13") (name "J5_D20_A5") (class "Default")
      (node (ref "D9") (pin "3") (pinfunction "CA_3") (pintype "passive"))
      (node (ref "IC1") (pin "36") (pinfunction "(S0:2/T1:0/AIN6)PA06_36") (pintype "bidirectional"))
      (node (ref "R36") (pin "2") (pinfunction "2_2") (pintype "passive"))
      (node (ref "R37") (pin "2") (pinfunction "2_2") (pintype "passive"))
      (node (ref "T5") (pin "5") (pinfunction "G_5") (pintype "passive"))
    )
    (net (code "14") (name "J6_D21_A6") (class "Default")
      (node (ref "D8") (pin "3") (pinfunction "CA_3") (pintype "passive"))
      (node (ref "IC1") (pin "37") (pinfunction "(S0:3/T1:1/AIN7)PA07_37") (pintype "bidirectional"))
      (node (ref "R39") (pin "2") (pinfunction "2_2") (pintype "passive"))
      (node (ref "R40") (pin "2") (pinfunction "2_2") (pintype "passive"))
      (node (ref "T4") (pin "2") (pinfunction "G_2") (pintype "passive"))
    )
    (net (code "15") (name "J7_D16_A1") (class "Default")
      (node (ref "D7") (pin "3") (pinfunction "CA_3") (pintype "passive"))
      (node (ref "IC1") (pin "27") (pinfunction "(S5:0/T6:0/AIN10)PB02_27") (pintype "bidirectional"))
      (node (ref "R42") (pin "2") (pinfunction "2_2") (pintype "passive"))
      (node (ref "R43") (pin "2") (pinfunction "2_2") (pintype "passive"))
      (node (ref "T4") (pin "5") (pinfunction "G_5") (pintype "passive"))
    )
    (net (code "16") (name "LED_SWCLK_D36") (class "Default")
      (node (ref "IC1") (pin "25") (pinfunction "(SWCLK/S1:2/T1:0)PA30_25") (pintype "bidirectional"))
      (node (ref "R14") (pin "1") (pinfunction "1_1") (pintype "passive"))
      (node (ref "SWCLK") (pin "1") (pinfunction "P_1") (pintype "passive"))
    )
    (net (code "17") (name "M1A_D7") (class "Default")
      (node (ref "IC1") (pin "14") (pinfunction "(S5:3|3:3/T7:1|0:7)PA21_14") (pintype "bidirectional"))
      (node (ref "IC3") (pin "4") (pinfunction "IN3_4") (pintype "bidirectional"))
    )
    (net (code "18") (name "M1B_D6") (class "Default")
      (node (ref "IC1") (pin "13") (pinfunction "(S5:2|3:2/T7:0|0:6)PA20_13") (pintype "bidirectional"))
      (node (ref "IC3") (pin "5") (pinfunction "IN4_5") (pintype "bidirectional"))
    )
    (net (code "19") (name "M2A_D1") (class "Default")
      (node (ref "IC1") (pin "16") (pinfunction "(SCL/S3:1|5:1/T4:1|0:5)PA23_16") (pintype "bidirectional"))
      (node (ref "IC3") (pin "1") (pinfunction "IN1_1") (pintype "bidirectional"))
    )
    (net (code "20") (name "M2B_D0") (class "Default")
      (node (ref "IC1") (pin "15") (pinfunction "(SDA/S3:0|5:0/T4:0|0:4)PA22_15") (pintype "bidirectional"))
      (node (ref "IC3") (pin "2") (pinfunction "IN2_2") (pintype "bidirectional"))
    )
    (net (code "21") (name "M3A_D3") (class "Default")
      (node (ref "IC1") (pin "41") (pinfunction "(S0:3|2:3/T1:1|0:3/AIN19)PA11_41") (pintype "bidirectional"))
      (node (ref "IC4") (pin "4") (pinfunction "IN3_4") (pintype "bidirectional"))
    )
    (net (code "22") (name "M3B_D2") (class "Default")
      (node (ref "IC1") (pin "40") (pinfunction "(S0:2|2:2/T1:0|0:2/AIN18)PA10_40") (pintype "bidirectional"))
      (node (ref "IC4") (pin "5") (pinfunction "IN4_5") (pintype "bidirectional"))
    )
    (net (code "23") (name "M4A_D5") (class "Default")
      (node (ref "IC1") (pin "44") (pinfunction "(S4:3/T5:1|0:5)PB11_44") (pintype "bidirectional"))
      (node (ref "IC4") (pin "1") (pinfunction "IN1_1") (pintype "bidirectional"))
    )
    (net (code "24") (name "M4B_D4") (class "Default")
      (node (ref "IC1") (pin "43") (pinfunction "(S4:2/T5:0|0:4)PB10_43") (pintype "bidirectional"))
      (node (ref "IC4") (pin "2") (pinfunction "IN2_2") (pintype "bidirectional"))
    )
    (net (code "25") (name "MISO_D10_LV") (class "Default")
      (node (ref "IC1") (pin "12") (pinfunction "(S1:3|3:3/T3:1|0:3)PA19_12") (pintype "bidirectional"))
      (node (ref "IC7") (pin "2") (pinfunction "SO/SIO1_2") (pintype "bidirectional"))
    )
    (net (code "26") (name "MOSI_D8_LV") (class "Default")
      (node (ref "IC1") (pin "8") (pinfunction "(SDA/S1:0|3:0/T2:0|0:6)PA16_8") (pintype "bidirectional"))
      (node (ref "IC7") (pin "5") (pinfunction "SI/SIO0_5") (pintype "bidirectional"))
    )
    (net (code "27") (name "Net-(C5-Pad2)") (class "Default")
      (node (ref "C5") (pin "2") (pinfunction "2_2") (pintype "passive"))
      (node (ref "R3") (pin "1") (pinfunction "1_1") (pintype "passive"))
    )
    (net (code "28") (name "Net-(IC1-(XIN32{slash}S1:0{slash}T2:0)PA00)") (class "Default")
      (node (ref "C17") (pin "1") (pinfunction "1_1") (pintype "passive"))
      (node (ref "IC1") (pin "29") (pinfunction "(XIN32/S1:0/T2:0)PA00_29") (pintype "bidirectional"))
      (node (ref "Q1") (pin "2") (pinfunction "2_2") (pintype "passive"))
    )
    (net (code "29") (name "Net-(IC1-(XOUT32{slash}S1:1{slash}T2:1)PA01)") (class "Default")
      (node (ref "C18") (pin "1") (pinfunction "1_1") (pintype "passive"))
      (node (ref "IC1") (pin "30") (pinfunction "(XOUT32/S1:1/T2:1)PA01_30") (pintype "bidirectional"))
      (node (ref "Q1") (pin "1") (pinfunction "1_1") (pintype "passive"))
    )
    (net (code "30") (name "Net-(IC1-5{slash}16{slash}LEDG)") (class "Default")
      (node (ref "IC1") (pin "46") (pinfunction "5/16/LEDG_46") (pintype "bidirectional"))
      (node (ref "R10") (pin "1") (pinfunction "1_1") (pintype "passive"))
    )
    (net (code "31") (name "Net-(IC1-6{slash}18{slash}LEDR)") (class "Default")
      (node (ref "IC1") (pin "47") (pinfunction "6/18/LEDR_47") (pintype "bidirectional"))
      (node (ref "R11") (pin "1") (pinfunction "1_1") (pintype "passive"))
    )
    (net (code "32") (name "Net-(IC3-OUT1)") (class "Default")
      (node (ref "IC3") (pin "10") (pinfunction "OUT1_10") (pintype "passive"))
      (node (ref "J7") (pin "2") (pinfunction "2_2") (pintype "passive"))
    )
    (net (code "33") (name "Net-(IC3-OUT2)") (class "Default")
      (node (ref "IC3") (pin "9") (pinfunction "OUT2_9") (pintype "passive"))
      (node (ref "J7") (pin "1") (pinfunction "1_1") (pintype "passive"))
    )
    (net (code "34") (name "Net-(IC3-OUT3)") (class "Default")
      (node (ref "IC3") (pin "7") (pinfunction "OUT3_7") (pintype "passive"))
      (node (ref "J9") (pin "2") (pinfunction "2_2") (pintype "passive"))
    )
    (net (code "35") (name "Net-(IC3-OUT4)") (class "Default")
      (node (ref "IC3") (pin "6") (pinfunction "OUT4_6") (pintype "passive"))
      (node (ref "J9") (pin "1") (pinfunction "1_1") (pintype "passive"))
    )
    (net (code "36") (name "Net-(IC4-OUT1)") (class "Default")
      (node (ref "IC4") (pin "10") (pinfunction "OUT1_10") (pintype "passive"))
      (node (ref "J10") (pin "2") (pinfunction "2_2") (pintype "passive"))
    )
    (net (code "37") (name "Net-(IC4-OUT2)") (class "Default")
      (node (ref "IC4") (pin "9") (pinfunction "OUT2_9") (pintype "passive"))
      (node (ref "J10") (pin "1") (pinfunction "1_1") (pintype "passive"))
    )
    (net (code "38") (name "Net-(IC4-OUT3)") (class "Default")
      (node (ref "IC4") (pin "7") (pinfunction "OUT3_7") (pintype "passive"))
      (node (ref "J11") (pin "2") (pinfunction "2_2") (pintype "passive"))
    )
    (net (code "39") (name "Net-(IC4-OUT4)") (class "Default")
      (node (ref "IC4") (pin "6") (pinfunction "OUT4_6") (pintype "passive"))
      (node (ref "J11") (pin "1") (pinfunction "1_1") (pintype "passive"))
    )
    (net (code "40") (name "Net-(IC6-BOOST)") (class "Default")
      (node (ref "C4") (pin "2") (pinfunction "2_2") (pintype "passive"))
      (node (ref "IC6") (pin "1") (pinfunction "BOOST_1") (pintype "passive"))
    )
    (net (code "41") (name "Net-(IC6-COMP)") (class "Default")
      (node (ref "IC6") (pin "6") (pinfunction "COMP_6") (pintype "passive"))
      (node (ref "R3") (pin "2") (pinfunction "2_2") (pintype "passive"))
    )
    (net (code "42") (name "Net-(IC6-EN)") (class "Default")
      (node (ref "IC6") (pin "7") (pinfunction "EN_7") (pintype "input"))
      (node (ref "R1") (pin "1") (pinfunction "1_1") (pintype "passive"))
      (node (ref "R2") (pin "2") (pinfunction "2_2") (pintype "passive"))
    )
    (net (code "43") (name "Net-(IC6-FB)") (class "Default")
      (node (ref "IC6") (pin "5") (pinfunction "FB_5") (pintype "passive"))
      (node (ref "R4") (pin "1") (pinfunction "1_1") (pintype "passive"))
      (node (ref "R5") (pin "2") (pinfunction "2_2") (pintype "passive"))
    )
    (net (code "44") (name "Net-(IC6-SS)") (class "Default")
      (node (ref "C3") (pin "2") (pinfunction "2_2") (pintype "passive"))
      (node (ref "IC6") (pin "8") (pinfunction "SS_8") (pintype "passive"))
    )
    (net (code "45") (name "Net-(IC6-SW)") (class "Default")
      (node (ref "C4") (pin "1") (pinfunction "1_1") (pintype "passive"))
      (node (ref "IC6") (pin "3") (pinfunction "SW_3") (pintype "passive"))
      (node (ref "L1") (pin "1") (pinfunction "1_1") (pintype "passive"))
    )
    (net (code "46") (name "Net-(IC6-VIN)") (class "Default")
      (node (ref "C1") (pin "2") (pinfunction "2_2") (pintype "passive"))
      (node (ref "C2") (pin "2") (pinfunction "2_2") (pintype "passive"))
      (node (ref "D1") (pin "C") (pinfunction "C_C") (pintype "passive"))
      (node (ref "D2") (pin "C") (pinfunction "C_C") (pintype "passive"))
      (node (ref "F1") (pin "1") (pinfunction "1_1") (pintype "passive"))
      (node (ref "IC6") (pin "2") (pinfunction "VIN_2") (pintype "power_in"))
      (node (ref "R1") (pin "2") (pinfunction "2_2") (pintype "passive"))
    )
    (net (code "47") (name "Net-(J1-Pad3)") (class "Default")
      (node (ref "J1") (pin "3") (pinfunction "3_3") (pintype "passive"))
      (node (ref "R27") (pin "1") (pinfunction "1_1") (pintype "passive"))
    )
    (net (code "48") (name "Net-(J2-Pad3)") (class "Default")
      (node (ref "J2") (pin "3") (pinfunction "3_3") (pintype "passive"))
      (node (ref "R30") (pin "1") (pinfunction "1_1") (pintype "passive"))
    )
    (net (code "49") (name "Net-(J3-Pad3)") (class "Default")
      (node (ref "J3") (pin "3") (pinfunction "3_3") (pintype "passive"))
      (node (ref "R33") (pin "1") (pinfunction "1_1") (pintype "passive"))
    )
    (net (code "50") (name "Net-(J4-Pad3)") (class "Default")
      (node (ref "J4") (pin "3") (pinfunction "3_3") (pintype "passive"))
      (node (ref "R36") (pin "1") (pinfunction "1_1") (pintype "passive"))
    )
    (net (code "51") (name "Net-(J5-Pad3)") (class "Default")
      (node (ref "J5") (pin "3") (pinfunction "3_3") (pintype "passive"))
      (node (ref "R39") (pin "1") (pinfunction "1_1") (pintype "passive"))
    )
    (net (code "52") (name "Net-(J6-Pad3)") (class "Default")
      (node (ref "J6") (pin "3") (pinfunction "3_3") (pintype "passive"))
      (node (ref "R42") (pin "1") (pinfunction "1_1") (pintype "passive"))
    )
    (net (code "53") (name "Net-(J8-Pad3)") (class "Default")
      (node (ref "J8") (pin "3") (pinfunction "3_3") (pintype "passive"))
      (node (ref "R24") (pin "1") (pinfunction "1_1") (pintype "passive"))
    )
    (net (code "54") (name "Net-(LED1-PadA)") (class "Default")
      (node (ref "LED1") (pin "A") (pinfunction "A_A") (pintype "passive"))
      (node (ref "R26") (pin "1") (pinfunction "1_1") (pintype "passive"))
    )
    (net (code "55") (name "Net-(LED2-PadA)") (class "Default")
      (node (ref "LED2") (pin "A") (pinfunction "A_A") (pintype "passive"))
      (node (ref "R29") (pin "1") (pinfunction "1_1") (pintype "passive"))
    )
    (net (code "56") (name "Net-(LED3-PadA)") (class "Default")
      (node (ref "LED3") (pin "A") (pinfunction "A_A") (pintype "passive"))
      (node (ref "R32") (pin "1") (pinfunction "1_1") (pintype "passive"))
    )
    (net (code "57") (name "Net-(LED4-PadA)") (class "Default")
      (node (ref "LED4") (pin "A") (pinfunction "A_A") (pintype "passive"))
      (node (ref "R35") (pin "1") (pinfunction "1_1") (pintype "passive"))
    )
    (net (code "58") (name "Net-(LED5-PadA)") (class "Default")
      (node (ref "LED5") (pin "A") (pinfunction "A_A") (pintype "passive"))
      (node (ref "R38") (pin "1") (pinfunction "1_1") (pintype "passive"))
    )
    (net (code "59") (name "Net-(LED6-PadA)") (class "Default")
      (node (ref "LED6") (pin "A") (pinfunction "A_A") (pintype "passive"))
      (node (ref "R41") (pin "1") (pinfunction "1_1") (pintype "passive"))
    )
    (net (code "60") (name "Net-(LED7-PadA)") (class "Default")
      (node (ref "LED7") (pin "A") (pinfunction "A_A") (pintype "passive"))
      (node (ref "R44") (pin "1") (pinfunction "1_1") (pintype "passive"))
    )
    (net (code "61") (name "Net-(LED8-PadA)") (class "Default")
      (node (ref "LED8") (pin "A") (pinfunction "A_A") (pintype "passive"))
      (node (ref "R22") (pin "2") (pinfunction "2_2") (pintype "passive"))
    )
    (net (code "62") (name "Net-(LED9-PadA)") (class "Default")
      (node (ref "LED9") (pin "A") (pinfunction "A_A") (pintype "passive"))
      (node (ref "R14") (pin "2") (pinfunction "2_2") (pintype "passive"))
    )
    (net (code "63") (name "Net-(LED16-PadA)") (class "Default")
      (node (ref "LED16") (pin "A") (pinfunction "A_A") (pintype "passive"))
      (node (ref "R10") (pin "2") (pinfunction "2_2") (pintype "passive"))
    )
    (net (code "64") (name "Net-(LED18-PadA)") (class "Default")
      (node (ref "LED18") (pin "A") (pinfunction "A_A") (pintype "passive"))
      (node (ref "R11") (pin "2") (pinfunction "2_2") (pintype "passive"))
    )
    (net (code "65") (name "Net-(R6-Pad2)") (class "Default")
      (node (ref "R6") (pin "2") (pinfunction "2_2") (pintype "passive"))
      (node (ref "USB") (pin "SHLD1") (pinfunction "SHIELD_SHLD1") (pintype "passive"))
      (node (ref "USB") (pin "SHLD2") (pinfunction "SHIELD_SHLD2") (pintype "passive"))
      (node (ref "USB") (pin "SHLD3") (pinfunction "SHIELD_SHLD3") (pintype "passive"))
    )
    (net (code "66") (name "Net-(R45-Pad2)") (class "Default")
      (node (ref "R45") (pin "2") (pinfunction "2_2") (pintype "passive"))
      (node (ref "RESET") (pin "2") (pinfunction "S1_2") (pintype "passive"))
      (node (ref "RESET") (pin "3") (pinfunction "S1_3") (pintype "passive"))
    )
    (net (code "67") (name "Net-(T1-D)") (class "Default")
      (node (ref "F2") (pin "2") (pinfunction "2_2") (pintype "passive"))
      (node (ref "T1") (pin "3") (pinfunction "D_3") (pintype "passive"))
    )
    (net (code "68") (name "Net-(T1-G)") (class "Default")
      (node (ref "R7") (pin "2") (pinfunction "2_2") (pintype "passive"))
      (node (ref "R8") (pin "1") (pinfunction "1_1") (pintype "passive"))
      (node (ref "T1") (pin "1") (pinfunction "G_1") (pintype "passive"))
    )
    (net (code "69") (name "Net-(T2-D)") (class "Default")
      (node (ref "D6") (pin "A") (pinfunction "A_A") (pintype "passive"))
      (node (ref "J12") (pin "2") (pinfunction "2_2") (pintype "passive"))
      (node (ref "T2") (pin "3") (pinfunction "D_3") (pintype "passive"))
    )
    (net (code "70") (name "Net-(T2-G)") (class "Default")
      (node (ref "R21") (pin "2") (pinfunction "2_2") (pintype "passive"))
      (node (ref "R22") (pin "1") (pinfunction "1_1") (pintype "passive"))
      (node (ref "R23") (pin "2") (pinfunction "2_2") (pintype "passive"))
      (node (ref "T2") (pin "1") (pinfunction "G_1") (pintype "passive"))
    )
    (net (code "71") (name "Net-(T4A-D)") (class "Default")
      (node (ref "LED6") (pin "C") (pinfunction "C_C") (pintype "passive"))
      (node (ref "T4") (pin "6") (pinfunction "D_6") (pintype "passive"))
    )
    (net (code "72") (name "Net-(T4B-D)") (class "Default")
      (node (ref "LED7") (pin "C") (pinfunction "C_C") (pintype "passive"))
      (node (ref "T4") (pin "3") (pinfunction "D_3") (pintype "passive"))
    )
    (net (code "73") (name "Net-(T5A-D)") (class "Default")
      (node (ref "LED4") (pin "C") (pinfunction "C_C") (pintype "passive"))
      (node (ref "T5") (pin "6") (pinfunction "D_6") (pintype "passive"))
    )
    (net (code "74") (name "Net-(T5B-D)") (class "Default")
      (node (ref "LED5") (pin "C") (pinfunction "C_C") (pintype "passive"))
      (node (ref "T5") (pin "3") (pinfunction "D_3") (pintype "passive"))
    )
    (net (code "75") (name "Net-(T6A-D)") (class "Default")
      (node (ref "LED2") (pin "C") (pinfunction "C_C") (pintype "passive"))
      (node (ref "T6") (pin "6") (pinfunction "D_6") (pintype "passive"))
    )
    (net (code "76") (name "Net-(T6B-D)") (class "Default")
      (node (ref "LED3") (pin "C") (pinfunction "C_C") (pintype "passive"))
      (node (ref "T6") (pin "3") (pinfunction "D_3") (pintype "passive"))
    )
    (net (code "77") (name "Net-(T7A-D)") (class "Default")
      (node (ref "LED1") (pin "C") (pinfunction "C_C") (pintype "passive"))
      (node (ref "T7") (pin "6") (pinfunction "D_6") (pintype "passive"))
    )
    (net (code "78") (name "RST") (class "Default")
      (node (ref "C14") (pin "2") (pinfunction "2_2") (pintype "passive"))
      (node (ref "IC1") (pin "24") (pinfunction "~{RESET}_24") (pintype "input"))
      (node (ref "R45") (pin "1") (pinfunction "1_1") (pintype "passive"))
      (node (ref "R9") (pin "2") (pinfunction "2_2") (pintype "passive"))
      (node (ref "RST") (pin "1") (pinfunction "P_1") (pintype "passive"))
    )
    (net (code "79") (name "RX_D13_LV") (class "Default")
      (node (ref "D15") (pin "3") (pinfunction "CA_3") (pintype "passive"))
      (node (ref "IC1") (pin "23") (pinfunction "(S5:3/T7:1)PB23_23") (pintype "bidirectional"))
      (node (ref "R46") (pin "1") (pinfunction "1_1") (pintype "passive"))
    )
    (net (code "80") (name "RX_HV") (class "Default")
      (node (ref "R46") (pin "2") (pinfunction "2_2") (pintype "passive"))
      (node (ref "UART") (pin "3") (pinfunction "3_3") (pintype "passive"))
    )
    (net (code "81") (name "S1_SWDIO_D37") (class "Default")
      (node (ref "IC1") (pin "26") (pinfunction "(SWDIO/S1:3/T1:1)PA31_26") (pintype "bidirectional"))
      (node (ref "R21") (pin "1") (pinfunction "1_1") (pintype "passive"))
      (node (ref "SWDIO") (pin "1") (pinfunction "P_1") (pintype "passive"))
    )
    (net (code "82") (name "SCK_D9_LV") (class "Default")
      (node (ref "IC1") (pin "9") (pinfunction "(SCL/S1:1|3:1/T2:1|0:7)PA17_9") (pintype "bidirectional"))
      (node (ref "IC7") (pin "6") (pinfunction "SCK_6") (pintype "bidirectional"))
    )
    (net (code "83") (name "SCL_D12_LV") (class "Default")
      (node (ref "IC1") (pin "39") (pinfunction "(SCL/S0:1|2:1/T0:1|1:3/AIN17)PA09_39") (pintype "bidirectional"))
      (node (ref "R15") (pin "1") (pinfunction "1_1") (pintype "passive"))
      (node (ref "T3") (pin "4") (pinfunction "S_4") (pintype "passive"))
    )
    (net (code "84") (name "SDA_D11_LV") (class "Default")
      (node (ref "IC1") (pin "38") (pinfunction "(SDA/S0:0|2:0/T0:0|1:2/AIN16)PA08_38") (pintype "bidirectional"))
      (node (ref "R17") (pin "1") (pinfunction "1_1") (pintype "passive"))
      (node (ref "T3") (pin "1") (pinfunction "S_1") (pintype "passive"))
    )
    (net (code "85") (name "TX_D14_LV") (class "Default")
      (node (ref "D16") (pin "3") (pinfunction "CA_3") (pintype "passive"))
      (node (ref "IC1") (pin "22") (pinfunction "(S5:2/T7:0)PB22_22") (pintype "bidirectional"))
      (node (ref "R47") (pin "1") (pinfunction "1_1") (pintype "passive"))
    )
    (net (code "86") (name "TX_HV") (class "Default")
      (node (ref "R47") (pin "2") (pinfunction "2_2") (pintype "passive"))
      (node (ref "UART") (pin "4") (pinfunction "4_4") (pintype "passive"))
    )
    (net (code "87") (name "USB_N") (class "Default")
      (node (ref "D-") (pin "1") (pinfunction "P_1") (pintype "passive"))
      (node (ref "D14") (pin "1") (pinfunction "C1_1") (pintype "passive"))
      (node (ref "IC1") (pin "18") (pinfunction "(USB_DM/S3:2|5:2/T5:0|1:2)PA24_18") (pintype "bidirectional"))
      (node (ref "USB") (pin "D-") (pinfunction "D-_D-") (pintype "bidirectional"))
    )
    (net (code "88") (name "USB_P") (class "Default")
      (node (ref "D+") (pin "1") (pinfunction "P_1") (pintype "passive"))
      (node (ref "D14") (pin "2") (pinfunction "C2_2") (pintype "passive"))
      (node (ref "IC1") (pin "19") (pinfunction "(USB_DP/S3:3|5:3/T5:1|1:3)PA25_19") (pintype "bidirectional"))
      (node (ref "USB") (pin "D+") (pinfunction "D+_D+") (pintype "bidirectional"))
    )
    (net (code "89") (name "V+") (class "Default")
      (node (ref "C19") (pin "1") (pinfunction "1_1") (pintype "passive"))
      (node (ref "C20") (pin "1") (pinfunction "1_1") (pintype "passive"))
      (node (ref "D6") (pin "C") (pinfunction "C_C") (pintype "passive"))
      (node (ref "F1") (pin "2") (pinfunction "2_2") (pintype "passive"))
      (node (ref "IC3") (pin "3") (pinfunction "VBB_3") (pintype "power_in"))
      (node (ref "IC4") (pin "3") (pinfunction "VBB_3") (pintype "power_in"))
      (node (ref "J12") (pin "1") (pinfunction "1_1") (pintype "passive"))
      (node (ref "R12") (pin "1") (pinfunction "1_1") (pintype "passive"))
    )
    (net (code "90") (name "VBUS") (class "Default")
      (node (ref "C10") (pin "2") (pinfunction "2_2") (pintype "passive"))
      (node (ref "F2") (pin "1") (pinfunction "1_1") (pintype "passive"))
      (node (ref "USB") (pin "VBUS") (pinfunction "VBUS_VBUS") (pintype "power_in"))
      (node (ref "VBUS") (pin "1") (pinfunction "P_1") (pintype "passive"))
    )
    (net (code "91") (name "VIN") (class "Default")
      (node (ref "D1") (pin "A") (pinfunction "A_A") (pintype "passive"))
      (node (ref "POWER") (pin "1") (pinfunction "1_1") (pintype "passive"))
      (node (ref "R8") (pin "2") (pinfunction "2_2") (pintype "passive"))
    )
    (net (code "92") (name "unconnected-(IC1-1{slash}RTC-Pad5)") (class "Default")
      (node (ref "IC1") (pin "5") (pinfunction "1/RTC_5") (pintype "bidirectional"))
    )
    (net (code "93") (name "unconnected-(IC1-3{slash}NC-Pad6)") (class "Default")
      (node (ref "IC1") (pin "6") (pinfunction "3/NC_6") (pintype "bidirectional"))
    )
    (net (code "94") (name "unconnected-(IC1-4{slash}15-Pad45)") (class "Default")
      (node (ref "IC1") (pin "45") (pinfunction "4/15_45") (pintype "bidirectional"))
    )
    (net (code "95") (name "unconnected-(IC1-CHIP_EN-Pad4)") (class "Default")
      (node (ref "IC1") (pin "4") (pinfunction "CHIP_EN_4") (pintype "input"))
    )
    (net (code "96") (name "unconnected-(IC1-RXD-Pad3)") (class "Default")
      (node (ref "IC1") (pin "3") (pinfunction "RXD_3") (pintype "input"))
    )
    (net (code "97") (name "unconnected-(IC1-SCL-Pad48)") (class "Default")
      (node (ref "IC1") (pin "48") (pinfunction "SCL_48") (pintype "bidirectional"))
    )
    (net (code "98") (name "unconnected-(IC1-SDA-Pad49)") (class "Default")
      (node (ref "IC1") (pin "49") (pinfunction "SDA_49") (pintype "bidirectional"))
    )
    (net (code "99") (name "unconnected-(IC1-TXD-Pad2)") (class "Default")
      (node (ref "IC1") (pin "2") (pinfunction "TXD_2") (pintype "output"))
    )
    (net (code "100") (name "unconnected-(IC1-W~{RESET}-Pad50)") (class "Default")
      (node (ref "IC1") (pin "50") (pinfunction "W~{RESET}_50") (pintype "input"))
    )
    (net (code "101") (name "unconnected-(USB-PadID)") (class "Default")
      (node (ref "USB") (pin "ID") (pinfunction "ID_ID") (pintype "bidirectional"))
    )
  )
)
